# RAK833BACKPLANE.net
KiCad netlist of a schematic drawn in EAGLE
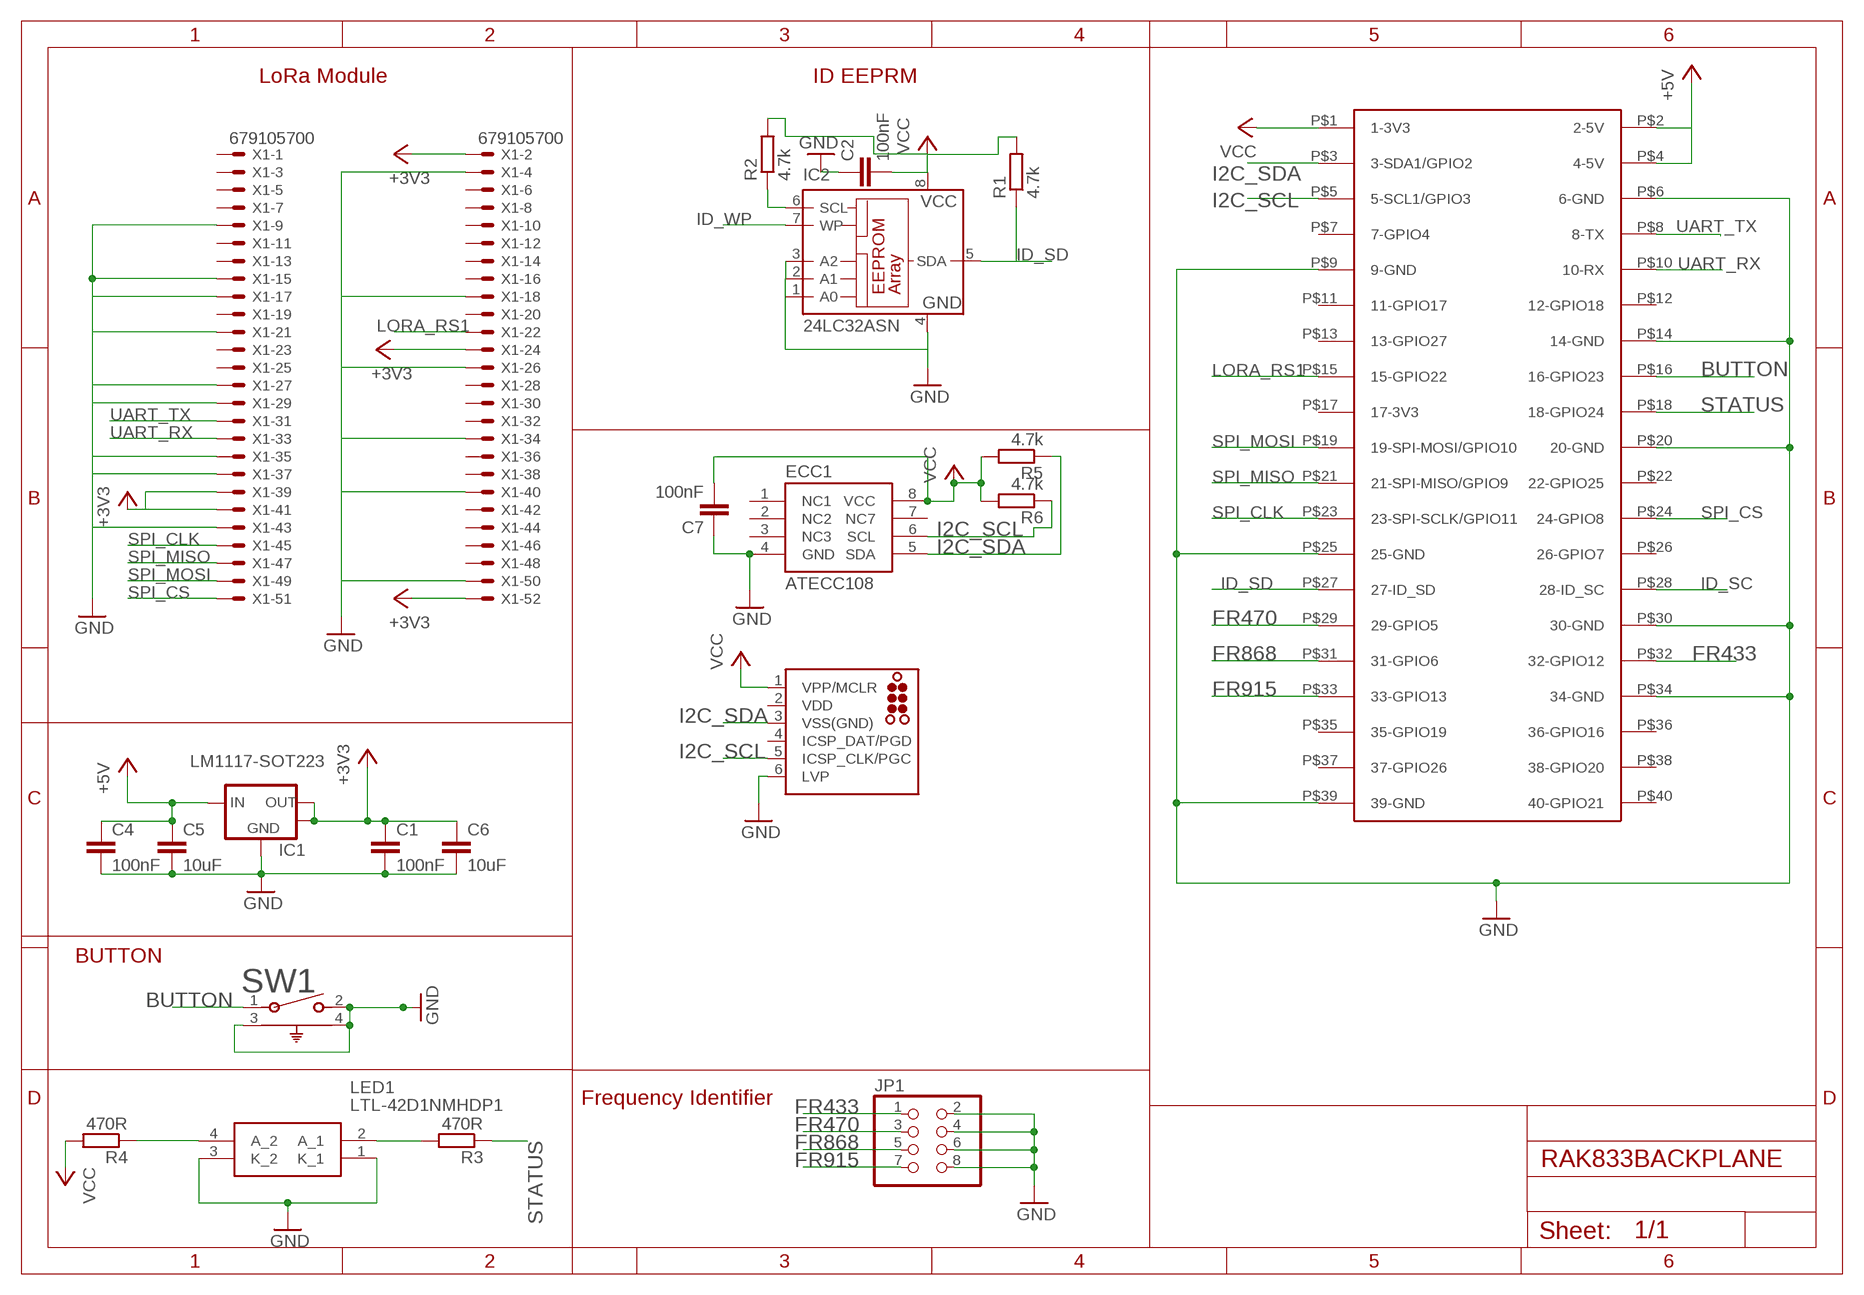
[diagram p0: schematic, sheet 1]

(export (version "E")
  (design (tool "Eeschema 10.0.6"))
  (components
    (comp (ref "C1")
      (value "100nF")
      (footprint "eagle-import:C0402")
      (libsource (lib "eagle-import") (part "C-EUC0402"))
    )
    (comp (ref "C2")
      (value "100nF")
      (footprint "eagle-import:C0402")
      (libsource (lib "eagle-import") (part "C-EUC0402"))
    )
    (comp (ref "C4")
      (value "100nF")
      (footprint "eagle-import:C0402")
      (libsource (lib "eagle-import") (part "C-EUC0402"))
    )
    (comp (ref "C5")
      (value "10uF")
      (footprint "eagle-import:C0603")
      (libsource (lib "eagle-import") (part "C-EUC0603"))
    )
    (comp (ref "C6")
      (value "10uF")
      (footprint "eagle-import:C0603")
      (libsource (lib "eagle-import") (part "C-EUC0603"))
    )
    (comp (ref "C7")
      (value "100nF")
      (footprint "eagle-import:C0402")
      (libsource (lib "eagle-import") (part "C-EUC0402"))
    )
    (comp (ref "ECC1")
      (value "ATECC108")
      (footprint "eagle-import:SO08")
      (libsource (lib "eagle-import") (part "ATECC108"))
    )
    (comp (ref "IC1")
      (value "LM1117-SOT223")
      (footprint "eagle-import:SOT-223-3")
      (libsource (lib "eagle-import") (part "LM1117-SOT223"))
    )
    (comp (ref "IC2")
      (value "24LC32ASN")
      (footprint "eagle-import:SO-08")
      (fields (field (name "MF") "MICROCHIP") (field (name "MPN") "24LC32A/SN"))
      (libsource (lib "eagle-import") (part "24SNLC32A"))
    )
    (comp (ref "J1")
      (value "TC2030-MCP-NL")
      (footprint "eagle-import:TC2030-MCP-NL")
      (libsource (lib "eagle-import") (part "TC2030-MCP-NL"))
    )
    (comp (ref "JP1")
      (value "PINHD-2X4")
      (footprint "eagle-import:2X04")
      (libsource (lib "eagle-import") (part "PINHD-2X4"))
    )
    (comp (ref "LED1")
      (value "LTL-42D1NMHDP1")
      (footprint "eagle-import:LTL42D1NMHDP1")
      (fields (field (name "MOUSER_PART_NUMBER") "859-LTL-42D1NMHDP1"))
      (libsource (lib "eagle-import") (part "LTL-42D1NMHDP1"))
    )
    (comp (ref "R1")
      (value "4.7k")
      (footprint "eagle-import:R0402")
      (libsource (lib "eagle-import") (part "R-EU_R0402"))
    )
    (comp (ref "R2")
      (value "4.7k")
      (footprint "eagle-import:R0402")
      (libsource (lib "eagle-import") (part "R-EU_R0402"))
    )
    (comp (ref "R3")
      (value "470R")
      (footprint "eagle-import:R0402")
      (libsource (lib "eagle-import") (part "R-EU_R0402"))
    )
    (comp (ref "R4")
      (value "470R")
      (footprint "eagle-import:R0402")
      (libsource (lib "eagle-import") (part "R-EU_R0402"))
    )
    (comp (ref "R5")
      (value "4.7k")
      (footprint "eagle-import:R0402")
      (libsource (lib "eagle-import") (part "R-EU_R0402"))
    )
    (comp (ref "R6")
      (value "4.7k")
      (footprint "eagle-import:R0402")
      (libsource (lib "eagle-import") (part "R-EU_R0402"))
    )
    (comp (ref "SW1")
      (value "1825027-8")
      (footprint "eagle-import:SW2_1825027-C_TEC")
      (fields (field (name "COPYRIGHT") "Copyright (C) 2016 Accelerated Designs. All rights reserved"))
      (libsource (lib "eagle-import") (part "1825027-8"))
    )
    (comp (ref "U$2")
      (value "RASPBERRY-PI+")
      (footprint "eagle-import:RASPBERRY-PI-PLUS-CAM_NOTCH")
      (libsource (lib "eagle-import") (part "RASPBERRY-PI+"))
    )
    (comp (ref "X1")
      (value "679105700")
      (footprint "eagle-import:679105700")
      (fields (field (name "MPN") "67910-5700"))
      (libsource (lib "eagle-import") (part "679105700"))
    )
  )
  (nets
    (net (code "1") (name "+3V3") (class "Default")
      (node (ref "C1") (pin "1") (pinfunction "1_1") (pintype "passive"))
      (node (ref "C6") (pin "1") (pinfunction "1_1") (pintype "passive"))
      (node (ref "IC1") (pin "2") (pinfunction "VOUT_2") (pintype "bidirectional"))
      (node (ref "IC1") (pin "4") (pinfunction "HEATSINK_4") (pintype "bidirectional"))
      (node (ref "X1") (pin "2") (pinfunction "S_2") (pintype "passive"))
      (node (ref "X1") (pin "24") (pinfunction "S_24") (pintype "passive"))
      (node (ref "X1") (pin "39") (pinfunction "S_39") (pintype "passive"))
      (node (ref "X1") (pin "41") (pinfunction "S_41") (pintype "passive"))
      (node (ref "X1") (pin "52") (pinfunction "S_52") (pintype "passive"))
    )
    (net (code "2") (name "+5V") (class "Default")
      (node (ref "C4") (pin "1") (pinfunction "1_1") (pintype "passive"))
      (node (ref "C5") (pin "1") (pinfunction "1_1") (pintype "passive"))
      (node (ref "IC1") (pin "3") (pinfunction "VIN_3") (pintype "bidirectional"))
      (node (ref "U$2") (pin "P$2") (pinfunction "2-5V_P$2") (pintype "bidirectional"))
      (node (ref "U$2") (pin "P$4") (pinfunction "4-5V_P$4") (pintype "bidirectional"))
    )
    (net (code "3") (name "/BUTTON") (class "Default")
      (node (ref "SW1") (pin "1") (pinfunction "1_1") (pintype "passive"))
      (node (ref "U$2") (pin "P$16") (pinfunction "16-GPIO23_P$16") (pintype "bidirectional"))
    )
    (net (code "4") (name "/FR433") (class "Default")
      (node (ref "JP1") (pin "1") (pinfunction "1_1") (pintype "passive"))
      (node (ref "U$2") (pin "P$32") (pinfunction "32-GPIO12_P$32") (pintype "bidirectional"))
    )
    (net (code "5") (name "/FR470") (class "Default")
      (node (ref "JP1") (pin "3") (pinfunction "3_3") (pintype "passive"))
      (node (ref "U$2") (pin "P$29") (pinfunction "29-GPIO5_P$29") (pintype "bidirectional"))
    )
    (net (code "6") (name "/FR868") (class "Default")
      (node (ref "JP1") (pin "5") (pinfunction "5_5") (pintype "passive"))
      (node (ref "U$2") (pin "P$31") (pinfunction "31-GPIO6_P$31") (pintype "bidirectional"))
    )
    (net (code "7") (name "/FR915") (class "Default")
      (node (ref "JP1") (pin "7") (pinfunction "7_7") (pintype "passive"))
      (node (ref "U$2") (pin "P$33") (pinfunction "33-GPIO13_P$33") (pintype "bidirectional"))
    )
    (net (code "8") (name "/I2C_SCL") (class "Default")
      (node (ref "ECC1") (pin "6") (pinfunction "SCL_6") (pintype "bidirectional"))
      (node (ref "J1") (pin "5") (pinfunction "ICSP_CLK/PGC_5") (pintype "output"))
      (node (ref "R6") (pin "1") (pinfunction "1_1") (pintype "passive"))
      (node (ref "U$2") (pin "P$5") (pinfunction "5-SCL1/GPIO3_P$5") (pintype "bidirectional"))
    )
    (net (code "9") (name "/I2C_SDA") (class "Default")
      (node (ref "ECC1") (pin "5") (pinfunction "SDA_5") (pintype "bidirectional"))
      (node (ref "J1") (pin "3") (pinfunction "VSS(GND)_3") (pintype "power_in"))
      (node (ref "R5") (pin "1") (pinfunction "1_1") (pintype "passive"))
      (node (ref "U$2") (pin "P$3") (pinfunction "3-SDA1/GPIO2_P$3") (pintype "bidirectional"))
    )
    (net (code "10") (name "/ID_SC") (class "Default")
      (node (ref "IC2") (pin "6") (pinfunction "SCL_6") (pintype "input"))
      (node (ref "R2") (pin "1") (pinfunction "1_1") (pintype "passive"))
      (node (ref "U$2") (pin "P$28") (pinfunction "28-ID_SC_P$28") (pintype "bidirectional"))
    )
    (net (code "11") (name "/ID_SD") (class "Default")
      (node (ref "IC2") (pin "5") (pinfunction "SDA_5") (pintype "bidirectional"))
      (node (ref "R1") (pin "1") (pinfunction "1_1") (pintype "passive"))
      (node (ref "U$2") (pin "P$27") (pinfunction "27-ID_SD_P$27") (pintype "bidirectional"))
    )
    (net (code "12") (name "/ID_WP") (class "Default")
      (node (ref "IC2") (pin "7") (pinfunction "WP_7") (pintype "input"))
    )
    (net (code "13") (name "/LORA_RS1") (class "Default")
      (node (ref "U$2") (pin "P$15") (pinfunction "15-GPIO22_P$15") (pintype "bidirectional"))
      (node (ref "X1") (pin "22") (pinfunction "S_22") (pintype "passive"))
    )
    (net (code "14") (name "/SPI_CLK") (class "Default")
      (node (ref "U$2") (pin "P$23") (pinfunction "23-SPI-SCLK/GPIO11_P$23") (pintype "bidirectional"))
      (node (ref "X1") (pin "45") (pinfunction "S_45") (pintype "passive"))
    )
    (net (code "15") (name "/SPI_CS") (class "Default")
      (node (ref "U$2") (pin "P$24") (pinfunction "24-GPIO8_P$24") (pintype "bidirectional"))
      (node (ref "X1") (pin "51") (pinfunction "S_51") (pintype "passive"))
    )
    (net (code "16") (name "/SPI_MISO") (class "Default")
      (node (ref "U$2") (pin "P$21") (pinfunction "21-SPI-MISO/GPIO9_P$21") (pintype "bidirectional"))
      (node (ref "X1") (pin "47") (pinfunction "S_47") (pintype "passive"))
    )
    (net (code "17") (name "/SPI_MOSI") (class "Default")
      (node (ref "U$2") (pin "P$19") (pinfunction "19-SPI-MOSI/GPIO10_P$19") (pintype "bidirectional"))
      (node (ref "X1") (pin "49") (pinfunction "S_49") (pintype "passive"))
    )
    (net (code "18") (name "/STATUS") (class "Default")
      (node (ref "R3") (pin "1") (pinfunction "1_1") (pintype "passive"))
      (node (ref "U$2") (pin "P$18") (pinfunction "18-GPIO24_P$18") (pintype "bidirectional"))
    )
    (net (code "19") (name "/UART_RX") (class "Default")
      (node (ref "U$2") (pin "P$10") (pinfunction "10-RX_P$10") (pintype "bidirectional"))
      (node (ref "X1") (pin "33") (pinfunction "S_33") (pintype "passive"))
    )
    (net (code "20") (name "/UART_TX") (class "Default")
      (node (ref "U$2") (pin "P$8") (pinfunction "8-TX_P$8") (pintype "bidirectional"))
      (node (ref "X1") (pin "31") (pinfunction "S_31") (pintype "passive"))
    )
    (net (code "21") (name "/VDD") (class "Default")
      (node (ref "J1") (pin "2") (pinfunction "VDD_2") (pintype "power_in"))
    )
    (net (code "22") (name "GND") (class "Default")
      (node (ref "C1") (pin "2") (pinfunction "2_2") (pintype "passive"))
      (node (ref "C2") (pin "1") (pinfunction "1_1") (pintype "passive"))
      (node (ref "C4") (pin "2") (pinfunction "2_2") (pintype "passive"))
      (node (ref "C5") (pin "2") (pinfunction "2_2") (pintype "passive"))
      (node (ref "C6") (pin "2") (pinfunction "2_2") (pintype "passive"))
      (node (ref "C7") (pin "1") (pinfunction "1_1") (pintype "passive"))
      (node (ref "ECC1") (pin "4") (pinfunction "GND_4") (pintype "power_in"))
      (node (ref "IC1") (pin "1") (pinfunction "GND_1") (pintype "bidirectional"))
      (node (ref "IC2") (pin "1") (pinfunction "A0_1") (pintype "input"))
      (node (ref "IC2") (pin "2") (pinfunction "A1_2") (pintype "input"))
      (node (ref "IC2") (pin "3") (pinfunction "A2_3") (pintype "input"))
      (node (ref "IC2") (pin "4") (pinfunction "GND_4") (pintype "power_in"))
      (node (ref "J1") (pin "6") (pinfunction "LVP_6") (pintype "bidirectional"))
      (node (ref "JP1") (pin "2") (pinfunction "2_2") (pintype "passive"))
      (node (ref "JP1") (pin "4") (pinfunction "4_4") (pintype "passive"))
      (node (ref "JP1") (pin "6") (pinfunction "6_6") (pintype "passive"))
      (node (ref "JP1") (pin "8") (pinfunction "8_8") (pintype "passive"))
      (node (ref "LED1") (pin "1") (pinfunction "K_1_1") (pintype "bidirectional"))
      (node (ref "LED1") (pin "3") (pinfunction "K_2_3") (pintype "bidirectional"))
      (node (ref "SW1") (pin "2") (pinfunction "2_2") (pintype "passive"))
      (node (ref "SW1") (pin "3") (pinfunction "3_3") (pintype "passive"))
      (node (ref "SW1") (pin "4") (pinfunction "4_4") (pintype "passive"))
      (node (ref "U$2") (pin "P$14") (pinfunction "14-GND_P$14") (pintype "bidirectional"))
      (node (ref "U$2") (pin "P$20") (pinfunction "20-GND_P$20") (pintype "bidirectional"))
      (node (ref "U$2") (pin "P$25") (pinfunction "25-GND_P$25") (pintype "bidirectional"))
      (node (ref "U$2") (pin "P$30") (pinfunction "30-GND_P$30") (pintype "bidirectional"))
      (node (ref "U$2") (pin "P$34") (pinfunction "34-GND_P$34") (pintype "bidirectional"))
      (node (ref "U$2") (pin "P$39") (pinfunction "39-GND_P$39") (pintype "bidirectional"))
      (node (ref "U$2") (pin "P$6") (pinfunction "6-GND_P$6") (pintype "bidirectional"))
      (node (ref "U$2") (pin "P$9") (pinfunction "9-GND_P$9") (pintype "bidirectional"))
      (node (ref "X1") (pin "15") (pinfunction "S_15") (pintype "passive"))
      (node (ref "X1") (pin "17") (pinfunction "S_17") (pintype "passive"))
      (node (ref "X1") (pin "21") (pinfunction "S_21") (pintype "passive"))
      (node (ref "X1") (pin "26") (pinfunction "S_26") (pintype "passive"))
      (node (ref "X1") (pin "27") (pinfunction "S_27") (pintype "passive"))
      (node (ref "X1") (pin "29") (pinfunction "S_29") (pintype "passive"))
      (node (ref "X1") (pin "34") (pinfunction "S_34") (pintype "passive"))
      (node (ref "X1") (pin "35") (pinfunction "S_35") (pintype "passive"))
      (node (ref "X1") (pin "37") (pinfunction "S_37") (pintype "passive"))
      (node (ref "X1") (pin "4") (pinfunction "S_4") (pintype "passive"))
      (node (ref "X1") (pin "40") (pinfunction "S_40") (pintype "passive"))
      (node (ref "X1") (pin "43") (pinfunction "S_43") (pintype "passive"))
      (node (ref "X1") (pin "50") (pinfunction "S_50") (pintype "passive"))
      (node (ref "X1") (pin "9") (pinfunction "S_9") (pintype "passive"))
    )
    (net (code "23") (name "Net-(LED1-A_1)") (class "Default")
      (node (ref "LED1") (pin "2") (pinfunction "A_1_2") (pintype "bidirectional"))
      (node (ref "R3") (pin "2") (pinfunction "2_2") (pintype "passive"))
    )
    (net (code "24") (name "Net-(LED1-A_2)") (class "Default")
      (node (ref "LED1") (pin "4") (pinfunction "A_2_4") (pintype "bidirectional"))
      (node (ref "R4") (pin "1") (pinfunction "1_1") (pintype "passive"))
    )
    (net (code "25") (name "VCC") (class "Default")
      (node (ref "C2") (pin "2") (pinfunction "2_2") (pintype "passive"))
      (node (ref "C7") (pin "2") (pinfunction "2_2") (pintype "passive"))
      (node (ref "ECC1") (pin "8") (pinfunction "VCC_8") (pintype "power_in"))
      (node (ref "IC2") (pin "8") (pinfunction "VCC_8") (pintype "power_in"))
      (node (ref "J1") (pin "1") (pinfunction "VPP/MCLR_1") (pintype "passive"))
      (node (ref "R1") (pin "2") (pinfunction "2_2") (pintype "passive"))
      (node (ref "R2") (pin "2") (pinfunction "2_2") (pintype "passive"))
      (node (ref "R4") (pin "2") (pinfunction "2_2") (pintype "passive"))
      (node (ref "R5") (pin "2") (pinfunction "2_2") (pintype "passive"))
      (node (ref "R6") (pin "2") (pinfunction "2_2") (pintype "passive"))
      (node (ref "U$2") (pin "P$1") (pinfunction "1-3V3_P$1") (pintype "bidirectional"))
    )
    (net (code "26") (name "unconnected-(ECC1-NC1-Pad1)") (class "Default")
      (node (ref "ECC1") (pin "1") (pinfunction "NC1_1") (pintype "bidirectional"))
    )
    (net (code "27") (name "unconnected-(ECC1-NC2-Pad2)") (class "Default")
      (node (ref "ECC1") (pin "2") (pinfunction "NC2_2") (pintype "no_connect"))
    )
    (net (code "28") (name "unconnected-(ECC1-NC3-Pad3)") (class "Default")
      (node (ref "ECC1") (pin "3") (pinfunction "NC3_3") (pintype "no_connect"))
    )
    (net (code "29") (name "unconnected-(ECC1-NC7-Pad7)") (class "Default")
      (node (ref "ECC1") (pin "7") (pinfunction "NC7_7") (pintype "no_connect"))
    )
    (net (code "30") (name "unconnected-(J1-ICSP_DAT{slash}PGD-Pad4)") (class "Default")
      (node (ref "J1") (pin "4") (pinfunction "ICSP_DAT/PGD_4") (pintype "bidirectional"))
    )
    (net (code "31") (name "unconnected-(U$2-7-GPIO4-PadP$7)") (class "Default")
      (node (ref "U$2") (pin "P$7") (pinfunction "7-GPIO4_P$7") (pintype "bidirectional"))
    )
    (net (code "32") (name "unconnected-(U$2-11-GPIO17-PadP$11)") (class "Default")
      (node (ref "U$2") (pin "P$11") (pinfunction "11-GPIO17_P$11") (pintype "bidirectional"))
    )
    (net (code "33") (name "unconnected-(U$2-12-GPIO18-PadP$12)") (class "Default")
      (node (ref "U$2") (pin "P$12") (pinfunction "12-GPIO18_P$12") (pintype "bidirectional"))
    )
    (net (code "34") (name "unconnected-(U$2-13-GPIO27-PadP$13)") (class "Default")
      (node (ref "U$2") (pin "P$13") (pinfunction "13-GPIO27_P$13") (pintype "bidirectional"))
    )
    (net (code "35") (name "unconnected-(U$2-17-3V3-PadP$17)") (class "Default")
      (node (ref "U$2") (pin "P$17") (pinfunction "17-3V3_P$17") (pintype "bidirectional"))
    )
    (net (code "36") (name "unconnected-(U$2-22-GPIO25-PadP$22)") (class "Default")
      (node (ref "U$2") (pin "P$22") (pinfunction "22-GPIO25_P$22") (pintype "bidirectional"))
    )
    (net (code "37") (name "unconnected-(U$2-26-GPIO7-PadP$26)") (class "Default")
      (node (ref "U$2") (pin "P$26") (pinfunction "26-GPIO7_P$26") (pintype "bidirectional"))
    )
    (net (code "38") (name "unconnected-(U$2-35-GPIO19-PadP$35)") (class "Default")
      (node (ref "U$2") (pin "P$35") (pinfunction "35-GPIO19_P$35") (pintype "bidirectional"))
    )
    (net (code "39") (name "unconnected-(U$2-36-GPIO16-PadP$36)") (class "Default")
      (node (ref "U$2") (pin "P$36") (pinfunction "36-GPIO16_P$36") (pintype "bidirectional"))
    )
    (net (code "40") (name "unconnected-(U$2-37-GPIO26-PadP$37)") (class "Default")
      (node (ref "U$2") (pin "P$37") (pinfunction "37-GPIO26_P$37") (pintype "bidirectional"))
    )
    (net (code "41") (name "unconnected-(U$2-38-GPIO20-PadP$38)") (class "Default")
      (node (ref "U$2") (pin "P$38") (pinfunction "38-GPIO20_P$38") (pintype "bidirectional"))
    )
    (net (code "42") (name "unconnected-(U$2-40-GPIO21-PadP$40)") (class "Default")
      (node (ref "U$2") (pin "P$40") (pinfunction "40-GPIO21_P$40") (pintype "bidirectional"))
    )
    (net (code "43") (name "unconnected-(X1A-S-Pad1)") (class "Default")
      (node (ref "X1") (pin "1") (pinfunction "S_1") (pintype "passive"))
    )
    (net (code "44") (name "unconnected-(X1AD-S-Pad36)") (class "Default")
      (node (ref "X1") (pin "36") (pinfunction "S_36") (pintype "passive"))
    )
    (net (code "45") (name "unconnected-(X1AF-S-Pad38)") (class "Default")
      (node (ref "X1") (pin "38") (pinfunction "S_38") (pintype "passive"))
    )
    (net (code "46") (name "unconnected-(X1AK-S-Pad42)") (class "Default")
      (node (ref "X1") (pin "42") (pinfunction "S_42") (pintype "passive"))
    )
    (net (code "47") (name "unconnected-(X1AM-S-Pad44)") (class "Default")
      (node (ref "X1") (pin "44") (pinfunction "S_44") (pintype "passive"))
    )
    (net (code "48") (name "unconnected-(X1AO-S-Pad46)") (class "Default")
      (node (ref "X1") (pin "46") (pinfunction "S_46") (pintype "passive"))
    )
    (net (code "49") (name "unconnected-(X1AQ-S-Pad48)") (class "Default")
      (node (ref "X1") (pin "48") (pinfunction "S_48") (pintype "passive"))
    )
    (net (code "50") (name "unconnected-(X1AS-S-Pad5)") (class "Default")
      (node (ref "X1") (pin "5") (pinfunction "S_5") (pintype "passive"))
    )
    (net (code "51") (name "unconnected-(X1AW-S-Pad6)") (class "Default")
      (node (ref "X1") (pin "6") (pinfunction "S_6") (pintype "passive"))
    )
    (net (code "52") (name "unconnected-(X1AX-S-Pad7)") (class "Default")
      (node (ref "X1") (pin "7") (pinfunction "S_7") (pintype "passive"))
    )
    (net (code "53") (name "unconnected-(X1AY-S-Pad8)") (class "Default")
      (node (ref "X1") (pin "8") (pinfunction "S_8") (pintype "passive"))
    )
    (net (code "54") (name "unconnected-(X1B-S-Pad10)") (class "Default")
      (node (ref "X1") (pin "10") (pinfunction "S_10") (pintype "passive"))
    )
    (net (code "55") (name "unconnected-(X1C-S-Pad11)") (class "Default")
      (node (ref "X1") (pin "11") (pinfunction "S_11") (pintype "passive"))
    )
    (net (code "56") (name "unconnected-(X1D-S-Pad12)") (class "Default")
      (node (ref "X1") (pin "12") (pinfunction "S_12") (pintype "passive"))
    )
    (net (code "57") (name "unconnected-(X1E-S-Pad13)") (class "Default")
      (node (ref "X1") (pin "13") (pinfunction "S_13") (pintype "passive"))
    )
    (net (code "58") (name "unconnected-(X1F-S-Pad14)") (class "Default")
      (node (ref "X1") (pin "14") (pinfunction "S_14") (pintype "passive"))
    )
    (net (code "59") (name "unconnected-(X1H-S-Pad16)") (class "Default")
      (node (ref "X1") (pin "16") (pinfunction "S_16") (pintype "passive"))
    )
    (net (code "60") (name "unconnected-(X1J-S-Pad18)") (class "Default")
      (node (ref "X1") (pin "18") (pinfunction "S_18") (pintype "passive"))
    )
    (net (code "61") (name "unconnected-(X1K-S-Pad19)") (class "Default")
      (node (ref "X1") (pin "19") (pinfunction "S_19") (pintype "passive"))
    )
    (net (code "62") (name "unconnected-(X1M-S-Pad20)") (class "Default")
      (node (ref "X1") (pin "20") (pinfunction "S_20") (pintype "passive"))
    )
    (net (code "63") (name "unconnected-(X1P-S-Pad23)") (class "Default")
      (node (ref "X1") (pin "23") (pinfunction "S_23") (pintype "passive"))
    )
    (net (code "64") (name "unconnected-(X1R-S-Pad25)") (class "Default")
      (node (ref "X1") (pin "25") (pinfunction "S_25") (pintype "passive"))
    )
    (net (code "65") (name "unconnected-(X1U-S-Pad28)") (class "Default")
      (node (ref "X1") (pin "28") (pinfunction "S_28") (pintype "passive"))
    )
    (net (code "66") (name "unconnected-(X1W-S-Pad3)") (class "Default")
      (node (ref "X1") (pin "3") (pinfunction "S_3") (pintype "passive"))
    )
    (net (code "67") (name "unconnected-(X1X-S-Pad30)") (class "Default")
      (node (ref "X1") (pin "30") (pinfunction "S_30") (pintype "passive"))
    )
    (net (code "68") (name "unconnected-(X1Z-S-Pad32)") (class "Default")
      (node (ref "X1") (pin "32") (pinfunction "S_32") (pintype "passive"))
    )
  )
)
